# core_ft232.net
KiCad netlist of a schematic drawn in EAGLE
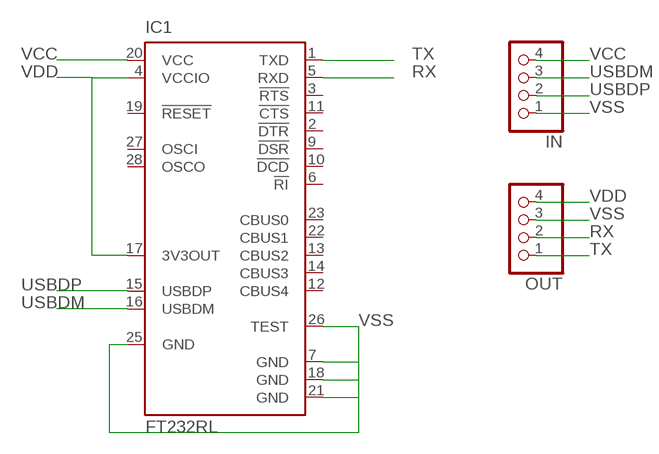
[diagram p0: schematic, sheet 1]

(export (version "E")
  (design (tool "Eeschema 10.0.6"))
  (components
    (comp (ref "IC1")
      (value "FT232RL")
      (footprint "eagle-import:SSOP28")
      (libsource (lib "eagle-import") (part "FT232RL"))
    )
    (comp (ref "IN")
      (value "PINHD-1X4")
      (footprint "eagle-import:1X04")
      (libsource (lib "eagle-import") (part "PINHD-1X4"))
    )
    (comp (ref "OUT")
      (value "PINHD-1X4")
      (footprint "eagle-import:1X04")
      (libsource (lib "eagle-import") (part "PINHD-1X4"))
    )
  )
  (nets
    (net (code "1") (name "/RX") (class "Default")
      (node (ref "IC1") (pin "5") (pinfunction "RXD_5") (pintype "input"))
      (node (ref "OUT") (pin "2") (pinfunction "2_2") (pintype "passive"))
    )
    (net (code "2") (name "/TX") (class "Default")
      (node (ref "IC1") (pin "1") (pinfunction "TXD_1") (pintype "output"))
      (node (ref "OUT") (pin "1") (pinfunction "1_1") (pintype "passive"))
    )
    (net (code "3") (name "/USBDM") (class "Default")
      (node (ref "IC1") (pin "16") (pinfunction "USBDM_16") (pintype "bidirectional"))
      (node (ref "IN") (pin "3") (pinfunction "3_3") (pintype "passive"))
    )
    (net (code "4") (name "/USBDP") (class "Default")
      (node (ref "IC1") (pin "15") (pinfunction "USBDP_15") (pintype "bidirectional"))
      (node (ref "IN") (pin "2") (pinfunction "2_2") (pintype "passive"))
    )
    (net (code "5") (name "/VCC") (class "Default")
      (node (ref "IC1") (pin "20") (pinfunction "VCC_20") (pintype "power_in"))
      (node (ref "IN") (pin "4") (pinfunction "4_4") (pintype "passive"))
    )
    (net (code "6") (name "/VDD") (class "Default")
      (node (ref "IC1") (pin "17") (pinfunction "3V3OUT_17") (pintype "output"))
      (node (ref "IC1") (pin "4") (pinfunction "VCCIO_4") (pintype "power_in"))
      (node (ref "OUT") (pin "4") (pinfunction "4_4") (pintype "passive"))
    )
    (net (code "7") (name "/VSS") (class "Default")
      (node (ref "IC1") (pin "18") (pinfunction "GND_18") (pintype "power_in"))
      (node (ref "IC1") (pin "21") (pinfunction "GND_21") (pintype "power_in"))
      (node (ref "IC1") (pin "25") (pinfunction "GND_25") (pintype "power_in"))
      (node (ref "IC1") (pin "26") (pinfunction "TEST_26") (pintype "input"))
      (node (ref "IC1") (pin "7") (pinfunction "GND_7") (pintype "power_in"))
      (node (ref "IN") (pin "1") (pinfunction "1_1") (pintype "passive"))
      (node (ref "OUT") (pin "3") (pinfunction "3_3") (pintype "passive"))
    )
    (net (code "8") (name "unconnected-(IC1-CBUS0-Pad23)") (class "Default")
      (node (ref "IC1") (pin "23") (pinfunction "CBUS0_23") (pintype "bidirectional"))
    )
    (net (code "9") (name "unconnected-(IC1-CBUS1-Pad22)") (class "Default")
      (node (ref "IC1") (pin "22") (pinfunction "CBUS1_22") (pintype "bidirectional"))
    )
    (net (code "10") (name "unconnected-(IC1-CBUS2-Pad13)") (class "Default")
      (node (ref "IC1") (pin "13") (pinfunction "CBUS2_13") (pintype "bidirectional"))
    )
    (net (code "11") (name "unconnected-(IC1-CBUS3-Pad14)") (class "Default")
      (node (ref "IC1") (pin "14") (pinfunction "CBUS3_14") (pintype "bidirectional"))
    )
    (net (code "12") (name "unconnected-(IC1-CBUS4-Pad12)") (class "Default")
      (node (ref "IC1") (pin "12") (pinfunction "CBUS4_12") (pintype "bidirectional"))
    )
    (net (code "13") (name "unconnected-(IC1-OSCI-Pad27)") (class "Default")
      (node (ref "IC1") (pin "27") (pinfunction "OSCI_27") (pintype "input"))
    )
    (net (code "14") (name "unconnected-(IC1-OSCO-Pad28)") (class "Default")
      (node (ref "IC1") (pin "28") (pinfunction "OSCO_28") (pintype "output"))
    )
    (net (code "15") (name "unconnected-(IC1-~{CTS}-Pad11)") (class "Default")
      (node (ref "IC1") (pin "11") (pinfunction "~{CTS}_11") (pintype "input"))
    )
    (net (code "16") (name "unconnected-(IC1-~{DCD}-Pad10)") (class "Default")
      (node (ref "IC1") (pin "10") (pinfunction "~{DCD}_10") (pintype "input"))
    )
    (net (code "17") (name "unconnected-(IC1-~{DSR}-Pad9)") (class "Default")
      (node (ref "IC1") (pin "9") (pinfunction "~{DSR}_9") (pintype "input"))
    )
    (net (code "18") (name "unconnected-(IC1-~{DTR}-Pad2)") (class "Default")
      (node (ref "IC1") (pin "2") (pinfunction "~{DTR}_2") (pintype "output"))
    )
    (net (code "19") (name "unconnected-(IC1-~{RESET}-Pad19)") (class "Default")
      (node (ref "IC1") (pin "19") (pinfunction "~{RESET}_19") (pintype "input"))
    )
    (net (code "20") (name "unconnected-(IC1-~{RI}-Pad6)") (class "Default")
      (node (ref "IC1") (pin "6") (pinfunction "~{RI}_6") (pintype "input"))
    )
    (net (code "21") (name "unconnected-(IC1-~{RTS}-Pad3)") (class "Default")
      (node (ref "IC1") (pin "3") (pinfunction "~{RTS}_3") (pintype "output"))
    )
  )
)
